# ltr-390uv-01-breakout.net
KiCad netlist of a schematic drawn in EAGLE
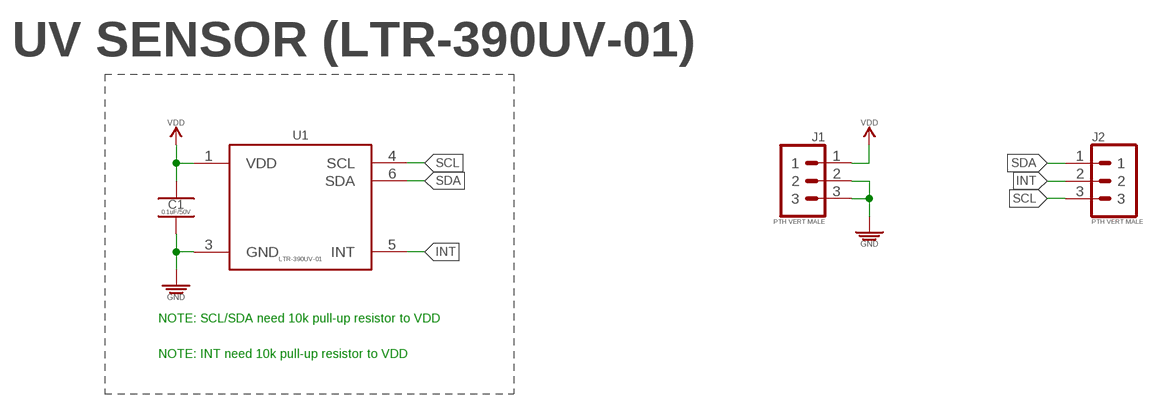
[diagram p0: schematic, sheet 1]

(export (version "E")
  (design (tool "Eeschema 10.0.6"))
  (components
    (comp (ref "C1")
      (value "0.1uF/50V")
      (footprint "eagle-import:CAPC1005X55_SMD-0402")
      (fields (field (name "MFR") "TDK Corporation") (field (name "MPN") "C1005X7R1H104K050BE"))
      (libsource (lib "eagle-import") (part "0.1UF_SMD-0402_50V-10%"))
    )
    (comp (ref "J1")
      (value "PTH VERT MALE")
      (footprint "eagle-import:HDRV3W64P254_1X3_762X254X838B")
      (fields (field (name "MFR") "Sullins Connector Solutions") (field (name "MPN") "PEC03SAAN"))
      (libsource (lib "eagle-import") (part "1X03_PTH_VERT_MALE_2.54MM"))
    )
    (comp (ref "J2")
      (value "PTH VERT MALE")
      (footprint "eagle-import:HDRV3W64P254_1X3_762X254X838B")
      (fields (field (name "MFR") "Sullins Connector Solutions") (field (name "MPN") "PEC03SAAN"))
      (libsource (lib "eagle-import") (part "1X03_PTH_VERT_MALE_2.54MM"))
    )
    (comp (ref "U1")
      (value "LTR-390UV-01")
      (footprint "eagle-import:SON65P200X200X70-6N-LTR-390UV-01")
      (fields (field (name "MFR") "Lite-On Inc."))
      (libsource (lib "eagle-import") (part "LTR-390UV-01"))
    )
  )
  (nets
    (net (code "1") (name "GND") (class "Default")
      (node (ref "C1") (pin "2") (pinfunction "2_2") (pintype "passive"))
      (node (ref "J1") (pin "2") (pinfunction "2_2") (pintype "passive"))
      (node (ref "J1") (pin "3") (pinfunction "3_3") (pintype "passive"))
      (node (ref "U1") (pin "3") (pinfunction "GND_3") (pintype "power_in"))
    )
    (net (code "2") (name "INT") (class "Default")
      (node (ref "J2") (pin "2") (pinfunction "2_2") (pintype "passive"))
      (node (ref "U1") (pin "5") (pinfunction "INT_5") (pintype "bidirectional"))
    )
    (net (code "3") (name "SCL") (class "Default")
      (node (ref "J2") (pin "3") (pinfunction "3_3") (pintype "passive"))
      (node (ref "U1") (pin "4") (pinfunction "SCL_4") (pintype "bidirectional"))
    )
    (net (code "4") (name "SDA") (class "Default")
      (node (ref "J2") (pin "1") (pinfunction "1_1") (pintype "passive"))
      (node (ref "U1") (pin "6") (pinfunction "SDA_6") (pintype "bidirectional"))
    )
    (net (code "5") (name "VDD") (class "Default")
      (node (ref "C1") (pin "1") (pinfunction "1_1") (pintype "passive"))
      (node (ref "J1") (pin "1") (pinfunction "1_1") (pintype "passive"))
      (node (ref "U1") (pin "1") (pinfunction "VDD_1") (pintype "power_in"))
    )
  )
)
